# Sensors.net
KiCad netlist of a schematic drawn in Altium Designer
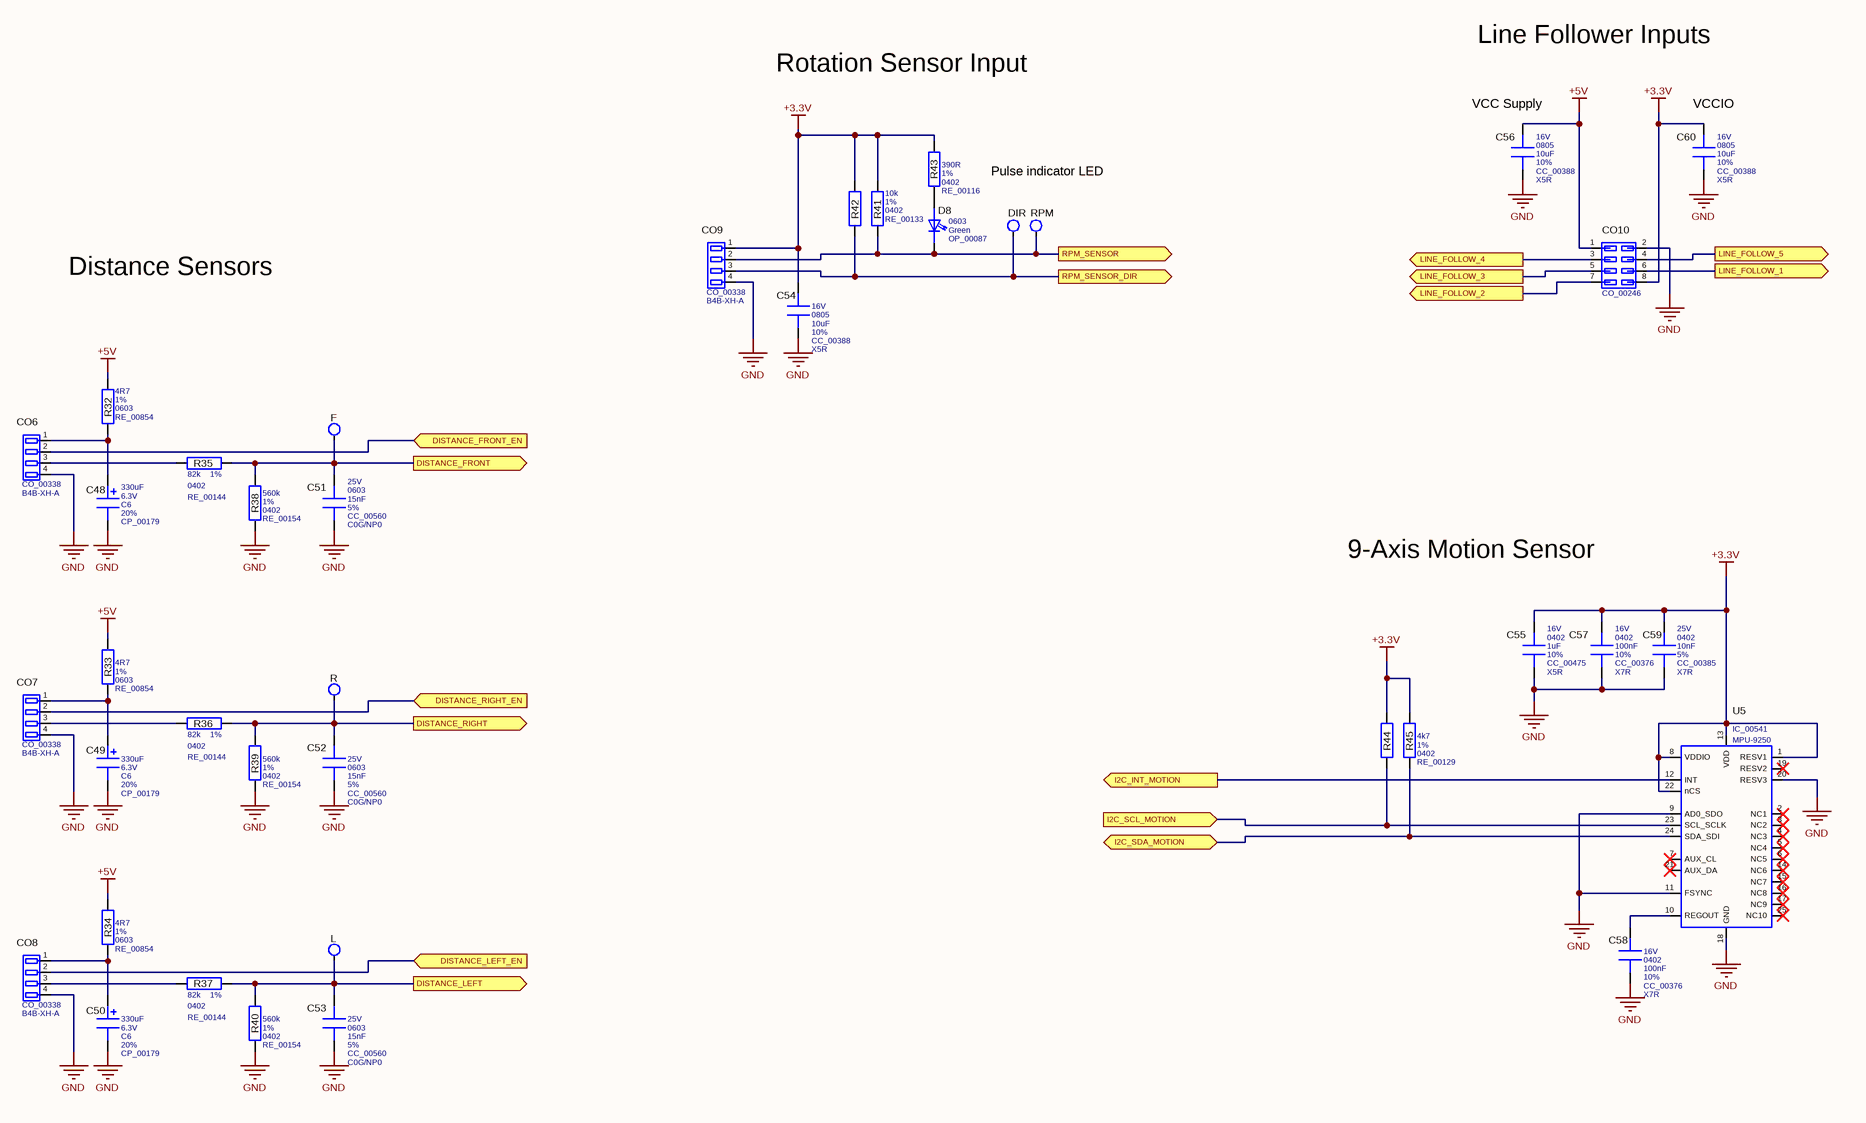
[diagram p0: Sensors.SchDoc]

(export (version "E")
  (design (tool "Eeschema 10.0.6"))
  (components
    (comp (ref "C48")
      (value "capacitor_polar")
      (footprint "CP_00179L")
      (fields
        (field (name "CAPACITANCE") "330uF")
        (field (name "VOLTAGE") "6.3V")
        (field (name "PACKAGE") "C6")
        (field (name "TOLERANCE") "20%")
        (field (name "PART_NUMBER") "CP_00179")
        (field (name "CREATOR") "Krenn Markus")
      )
      (libsource (lib "Central Library") (part "capacitor_polar"))
    )
    (comp (ref "C49")
      (value "capacitor_polar")
      (footprint "CP_00179L")
      (fields
        (field (name "CAPACITANCE") "330uF")
        (field (name "VOLTAGE") "6.3V")
        (field (name "PACKAGE") "C6")
        (field (name "TOLERANCE") "20%")
        (field (name "PART_NUMBER") "CP_00179")
        (field (name "CREATOR") "Krenn Markus")
      )
      (libsource (lib "Central Library") (part "capacitor_polar"))
    )
    (comp (ref "C50")
      (value "capacitor_polar")
      (footprint "CP_00179L")
      (fields
        (field (name "CAPACITANCE") "330uF")
        (field (name "VOLTAGE") "6.3V")
        (field (name "PACKAGE") "C6")
        (field (name "TOLERANCE") "20%")
        (field (name "PART_NUMBER") "CP_00179")
        (field (name "CREATOR") "Krenn Markus")
      )
      (libsource (lib "Central Library") (part "capacitor_polar"))
    )
    (comp (ref "C51")
      (value "capacitor")
      (footprint "CS1600X800X900X350X1250L")
      (fields
        (field (name "VOLTAGE") "25V")
        (field (name "PACKAGE") "0603")
        (field (name "CAPACITANCE") "15nF")
        (field (name "TOLERANCE") "5%")
        (field (name "PART_NUMBER") "CC_00560")
        (field (name "DIELECTRIC_MATERIAL") "C0G/NP0")
        (field (name "CREATOR") "Krenn Markus")
      )
      (libsource (lib "Central Library") (part "capacitor"))
    )
    (comp (ref "C52")
      (value "capacitor")
      (footprint "CS1600X800X900X350X1250L")
      (fields
        (field (name "VOLTAGE") "25V")
        (field (name "PACKAGE") "0603")
        (field (name "CAPACITANCE") "15nF")
        (field (name "TOLERANCE") "5%")
        (field (name "PART_NUMBER") "CC_00560")
        (field (name "DIELECTRIC_MATERIAL") "C0G/NP0")
        (field (name "CREATOR") "Krenn Markus")
      )
      (libsource (lib "Central Library") (part "capacitor"))
    )
    (comp (ref "C53")
      (value "capacitor")
      (footprint "CS1600X800X900X350X1250L")
      (fields
        (field (name "VOLTAGE") "25V")
        (field (name "PACKAGE") "0603")
        (field (name "CAPACITANCE") "15nF")
        (field (name "TOLERANCE") "5%")
        (field (name "PART_NUMBER") "CC_00560")
        (field (name "DIELECTRIC_MATERIAL") "C0G/NP0")
        (field (name "CREATOR") "Krenn Markus")
      )
      (libsource (lib "Central Library") (part "capacitor"))
    )
    (comp (ref "C54")
      (value "capacitor")
      (footprint "CS2000x1250x1250x350x1650L")
      (fields
        (field (name "VOLTAGE") "16V")
        (field (name "PACKAGE") "0805")
        (field (name "CAPACITANCE") "10uF")
        (field (name "TOLERANCE") "10%")
        (field (name "PART_NUMBER") "CC_00388")
        (field (name "DIELECTRIC_MATERIAL") "X5R")
        (field (name "CREATOR") "Krenn Markus")
      )
      (libsource (lib "Central Library") (part "capacitor"))
    )
    (comp (ref "C55")
      (value "capacitor")
      (footprint "CS1000X500X560X250X820L")
      (fields
        (field (name "VOLTAGE") "16V")
        (field (name "PACKAGE") "0402")
        (field (name "CAPACITANCE") "1uF")
        (field (name "TOLERANCE") "10%")
        (field (name "PART_NUMBER") "CC_00475")
        (field (name "DIELECTRIC_MATERIAL") "X5R")
        (field (name "CREATOR") "Krenn Markus")
      )
      (libsource (lib "Central Library") (part "capacitor"))
    )
    (comp (ref "C56")
      (value "capacitor")
      (footprint "CS2000x1250x1250x350x1650L")
      (fields
        (field (name "VOLTAGE") "16V")
        (field (name "PACKAGE") "0805")
        (field (name "CAPACITANCE") "10uF")
        (field (name "TOLERANCE") "10%")
        (field (name "PART_NUMBER") "CC_00388")
        (field (name "DIELECTRIC_MATERIAL") "X5R")
        (field (name "CREATOR") "Krenn Markus")
      )
      (libsource (lib "Central Library") (part "capacitor"))
    )
    (comp (ref "C57")
      (value "capacitor")
      (footprint "CS1000X500X560X250X820L")
      (fields
        (field (name "VOLTAGE") "16V")
        (field (name "PACKAGE") "0402")
        (field (name "CAPACITANCE") "100nF")
        (field (name "TOLERANCE") "10%")
        (field (name "PART_NUMBER") "CC_00376")
        (field (name "DIELECTRIC_MATERIAL") "X7R")
        (field (name "CREATOR") "Okorn Robert")
      )
      (libsource (lib "Central Library") (part "capacitor"))
    )
    (comp (ref "C58")
      (value "capacitor")
      (footprint "CS1000X500X560X250X820L")
      (fields
        (field (name "VOLTAGE") "16V")
        (field (name "PACKAGE") "0402")
        (field (name "CAPACITANCE") "100nF")
        (field (name "TOLERANCE") "10%")
        (field (name "PART_NUMBER") "CC_00376")
        (field (name "DIELECTRIC_MATERIAL") "X7R")
        (field (name "CREATOR") "Okorn Robert")
      )
      (libsource (lib "Central Library") (part "capacitor"))
    )
    (comp (ref "C59")
      (value "capacitor")
      (footprint "CS1000X500X560X250X820L")
      (fields
        (field (name "VOLTAGE") "25V")
        (field (name "PACKAGE") "0402")
        (field (name "CAPACITANCE") "10nF")
        (field (name "TOLERANCE") "5%")
        (field (name "PART_NUMBER") "CC_00385")
        (field (name "DIELECTRIC_MATERIAL") "X7R")
        (field (name "CREATOR") "Neissl Gernot")
      )
      (libsource (lib "Central Library") (part "capacitor"))
    )
    (comp (ref "C60")
      (value "capacitor")
      (footprint "CS2000x1250x1250x350x1650L")
      (fields
        (field (name "VOLTAGE") "16V")
        (field (name "PACKAGE") "0805")
        (field (name "CAPACITANCE") "10uF")
        (field (name "TOLERANCE") "10%")
        (field (name "PART_NUMBER") "CC_00388")
        (field (name "DIELECTRIC_MATERIAL") "X5R")
        (field (name "CREATOR") "Krenn Markus")
      )
      (libsource (lib "Central Library") (part "capacitor"))
    )
    (comp (ref "CO6")
      (value "header1x4")
      (footprint "CO_00338N")
      (description "XH connector - Disconnectable Crimp style connectors")
      (fields
        (field (name "POWER") "0W")
        (field (name "PART_NUMBER") "CO_00338")
        (field (name "MANUFACTURER_NUMBER") "B4B-XH-A")
        (field (name "CREATOR") "Krenn Markus")
      )
      (libsource (lib "Central Library") (part "header1x4"))
    )
    (comp (ref "CO7")
      (value "header1x4")
      (footprint "CO_00338N")
      (description "XH connector - Disconnectable Crimp style connectors")
      (fields
        (field (name "POWER") "0W")
        (field (name "PART_NUMBER") "CO_00338")
        (field (name "MANUFACTURER_NUMBER") "B4B-XH-A")
        (field (name "CREATOR") "Krenn Markus")
      )
      (libsource (lib "Central Library") (part "header1x4"))
    )
    (comp (ref "CO8")
      (value "header1x4")
      (footprint "CO_00338N")
      (description "XH connector - Disconnectable Crimp style connectors")
      (fields
        (field (name "POWER") "0W")
        (field (name "PART_NUMBER") "CO_00338")
        (field (name "MANUFACTURER_NUMBER") "B4B-XH-A")
        (field (name "CREATOR") "Krenn Markus")
      )
      (libsource (lib "Central Library") (part "header1x4"))
    )
    (comp (ref "CO9")
      (value "header1x4")
      (footprint "CO_00338N")
      (description "XH connector - Disconnectable Crimp style connectors")
      (fields
        (field (name "POWER") "0W")
        (field (name "PART_NUMBER") "CO_00338")
        (field (name "MANUFACTURER_NUMBER") "B4B-XH-A")
        (field (name "CREATOR") "Krenn Markus")
      )
      (libsource (lib "Central Library") (part "header1x4"))
    )
    (comp (ref "CO10")
      (value "header2x4")
      (footprint "CO_00246N")
      (description "SMT .025\" SQ POST HEADER")
      (fields
        (field (name "POWER") "0W")
        (field (name "PART_NUMBER") "CO_00246")
        (field (name "CREATOR") "Krenn Markus")
      )
      (libsource (lib "Central Library") (part "header2x4"))
    )
    (comp (ref "D8")
      (value "LED")
      (footprint "OP_00087L")
      (fields
        (field (name "PACKAGE") "0603")
        (field (name "COLOR") "Green")
        (field (name "PART_NUMBER") "OP_00087")
        (field (name "CREATOR") "Krenn Markus")
      )
      (libsource (lib "Central Library") (part "LED"))
    )
    (comp (ref "DIR")
      (value "testpoint")
      (footprint "CO_00057N")
      (description "Testpoint 1.6mm Bohrung 1mm")
      (fields
        (field (name "PART_NUMBER") "CO_00057")
        (field (name "POWER") "0W")
        (field (name "CREATOR") "Sirnik Heimo")
      )
      (libsource (lib "Central Library") (part "testpoint"))
    )
    (comp (ref "F")
      (value "testpoint")
      (footprint "CO_00057N")
      (description "Testpoint 1.6mm Bohrung 1mm")
      (fields
        (field (name "PART_NUMBER") "CO_00057")
        (field (name "POWER") "0W")
        (field (name "CREATOR") "Sirnik Heimo")
      )
      (libsource (lib "Central Library") (part "testpoint"))
    )
    (comp (ref "L")
      (value "testpoint")
      (footprint "CO_00057N")
      (description "Testpoint 1.6mm Bohrung 1mm")
      (fields
        (field (name "PART_NUMBER") "CO_00057")
        (field (name "POWER") "0W")
        (field (name "CREATOR") "Sirnik Heimo")
      )
      (libsource (lib "Central Library") (part "testpoint"))
    )
    (comp (ref "R")
      (value "testpoint")
      (footprint "CO_00057N")
      (description "Testpoint 1.6mm Bohrung 1mm")
      (fields
        (field (name "PART_NUMBER") "CO_00057")
        (field (name "POWER") "0W")
        (field (name "CREATOR") "Sirnik Heimo")
      )
      (libsource (lib "Central Library") (part "testpoint"))
    )
    (comp (ref "R32")
      (value "Resistor")
      (footprint "RS1600X850X450X300X1300L")
      (fields
        (field (name "RESISTANCE") "4R7")
        (field (name "TOLERANCE") "1%")
        (field (name "PACKAGE") "0603")
        (field (name "PART_NUMBER") "RE_00854")
        (field (name "CREATOR") "Krenn Markus")
      )
      (libsource (lib "Central Library") (part "Resistor"))
    )
    (comp (ref "R33")
      (value "Resistor")
      (footprint "RS1600X850X450X300X1300L")
      (fields
        (field (name "RESISTANCE") "4R7")
        (field (name "TOLERANCE") "1%")
        (field (name "PACKAGE") "0603")
        (field (name "PART_NUMBER") "RE_00854")
        (field (name "CREATOR") "Krenn Markus")
      )
      (libsource (lib "Central Library") (part "Resistor"))
    )
    (comp (ref "R34")
      (value "Resistor")
      (footprint "RS1600X850X450X300X1300L")
      (fields
        (field (name "RESISTANCE") "4R7")
        (field (name "TOLERANCE") "1%")
        (field (name "PACKAGE") "0603")
        (field (name "PART_NUMBER") "RE_00854")
        (field (name "CREATOR") "Krenn Markus")
      )
      (libsource (lib "Central Library") (part "Resistor"))
    )
    (comp (ref "R35")
      (value "Resistor")
      (footprint "RS1000X500X560X250X820L")
      (fields
        (field (name "RESISTANCE") "82k")
        (field (name "TOLERANCE") "1%")
        (field (name "PACKAGE") "0402")
        (field (name "PART_NUMBER") "RE_00144")
        (field (name "CREATOR") "Krenn Markus")
      )
      (libsource (lib "Central Library") (part "Resistor"))
    )
    (comp (ref "R36")
      (value "Resistor")
      (footprint "RS1000X500X560X250X820L")
      (fields
        (field (name "RESISTANCE") "82k")
        (field (name "TOLERANCE") "1%")
        (field (name "PACKAGE") "0402")
        (field (name "PART_NUMBER") "RE_00144")
        (field (name "CREATOR") "Krenn Markus")
      )
      (libsource (lib "Central Library") (part "Resistor"))
    )
    (comp (ref "R37")
      (value "Resistor")
      (footprint "RS1000X500X560X250X820L")
      (fields
        (field (name "RESISTANCE") "82k")
        (field (name "TOLERANCE") "1%")
        (field (name "PACKAGE") "0402")
        (field (name "PART_NUMBER") "RE_00144")
        (field (name "CREATOR") "Krenn Markus")
      )
      (libsource (lib "Central Library") (part "Resistor"))
    )
    (comp (ref "R38")
      (value "Resistor")
      (footprint "RS1000X500X560X250X820L")
      (fields
        (field (name "RESISTANCE") "560k")
        (field (name "TOLERANCE") "1%")
        (field (name "PACKAGE") "0402")
        (field (name "PART_NUMBER") "RE_00154")
        (field (name "CREATOR") "Krenn Markus")
      )
      (libsource (lib "Central Library") (part "Resistor"))
    )
    (comp (ref "R39")
      (value "Resistor")
      (footprint "RS1000X500X560X250X820L")
      (fields
        (field (name "RESISTANCE") "560k")
        (field (name "TOLERANCE") "1%")
        (field (name "PACKAGE") "0402")
        (field (name "PART_NUMBER") "RE_00154")
        (field (name "CREATOR") "Krenn Markus")
      )
      (libsource (lib "Central Library") (part "Resistor"))
    )
    (comp (ref "R40")
      (value "Resistor")
      (footprint "RS1000X500X560X250X820L")
      (fields
        (field (name "RESISTANCE") "560k")
        (field (name "TOLERANCE") "1%")
        (field (name "PACKAGE") "0402")
        (field (name "PART_NUMBER") "RE_00154")
        (field (name "CREATOR") "Krenn Markus")
      )
      (libsource (lib "Central Library") (part "Resistor"))
    )
    (comp (ref "R41")
      (value "Resistor")
      (footprint "RS1000X500X560X250X820L")
      (fields
        (field (name "RESISTANCE") "10k")
        (field (name "TOLERANCE") "1%")
        (field (name "PACKAGE") "0402")
        (field (name "PART_NUMBER") "RE_00133")
        (field (name "CREATOR") "Krenn Markus")
      )
      (libsource (lib "Central Library") (part "Resistor"))
    )
    (comp (ref "R42")
      (value "Resistor")
      (footprint "RS1000X500X560X250X820L")
      (fields
        (field (name "TOLERANCE") "1%")
        (field (name "PART_NUMBER") "RE_00133")
        (field (name "CREATOR") "Krenn Markus")
      )
      (libsource (lib "Central Library") (part "Resistor"))
    )
    (comp (ref "R43")
      (value "Resistor")
      (footprint "RS1000X500X560X250X820L")
      (fields
        (field (name "RESISTANCE") "390R")
        (field (name "TOLERANCE") "1%")
        (field (name "PACKAGE") "0402")
        (field (name "PART_NUMBER") "RE_00116")
        (field (name "CREATOR") "Krenn Markus")
      )
      (libsource (lib "Central Library") (part "Resistor"))
    )
    (comp (ref "R44")
      (value "Resistor")
      (footprint "RS1000X500X560X250X820L")
      (fields
        (field (name "TOLERANCE") "1%")
        (field (name "PART_NUMBER") "RE_00129")
        (field (name "CREATOR") "Krenn Markus")
      )
      (libsource (lib "Central Library") (part "Resistor"))
    )
    (comp (ref "R45")
      (value "Resistor")
      (footprint "RS1000X500X560X250X820L")
      (fields
        (field (name "RESISTANCE") "4k7")
        (field (name "TOLERANCE") "1%")
        (field (name "PACKAGE") "0402")
        (field (name "PART_NUMBER") "RE_00129")
        (field (name "CREATOR") "Krenn Markus")
      )
      (libsource (lib "Central Library") (part "Resistor"))
    )
    (comp (ref "RPM")
      (value "testpoint")
      (footprint "CO_00057N")
      (description "Testpoint 1.6mm Bohrung 1mm")
      (fields
        (field (name "PART_NUMBER") "CO_00057")
        (field (name "POWER") "0W")
        (field (name "CREATOR") "Sirnik Heimo")
      )
      (libsource (lib "Central Library") (part "testpoint"))
    )
    (comp (ref "U5")
      (value "IC_00541")
      (footprint "IC_00541N")
      (description "MPU-9250 - GYRO/ACCEL/COMPASS, 9ACHSEN, I2C, QFN-24")
      (fields
        (field (name "PART_NUMBER") "IC_00541")
        (field (name "MANUFACTURER_NUMBER") "MPU-9250")
        (field (name "CREATOR") "Sirnik Heimo")
      )
      (libsource (lib "Central Library") (part "IC_00541"))
    )
  )
  (nets
    (net (code "1") (name "+3.3V") (class "Default")
      (node (ref "C54") (pin "2") (pinfunction "PIN2_2") (pintype "passive"))
      (node (ref "C55") (pin "2") (pinfunction "PIN2_2") (pintype "passive"))
      (node (ref "C57") (pin "2") (pinfunction "PIN2_2") (pintype "passive"))
      (node (ref "C59") (pin "2") (pinfunction "PIN2_2") (pintype "passive"))
      (node (ref "C60") (pin "2") (pinfunction "PIN2_2") (pintype "passive"))
      (node (ref "CO10") (pin "8") (pinfunction "PIN8_8") (pintype "passive"))
      (node (ref "CO9") (pin "1") (pinfunction "PIN1_1") (pintype "passive"))
      (node (ref "R41") (pin "2") (pinfunction "PIN2_2") (pintype "passive"))
      (node (ref "R42") (pin "2") (pinfunction "PIN2_2") (pintype "passive"))
      (node (ref "R43") (pin "2") (pinfunction "PIN2_2") (pintype "passive"))
      (node (ref "R44") (pin "2") (pinfunction "PIN2_2") (pintype "passive"))
      (node (ref "R45") (pin "2") (pinfunction "PIN2_2") (pintype "passive"))
      (node (ref "U5") (pin "1") (pinfunction "RESV1_1") (pintype "passive"))
      (node (ref "U5") (pin "13") (pinfunction "VDD_13") (pintype "passive"))
      (node (ref "U5") (pin "22") (pinfunction "nCS_22") (pintype "passive"))
      (node (ref "U5") (pin "8") (pinfunction "VDDIO_8") (pintype "passive"))
    )
    (net (code "2") (name "+5V") (class "Default")
      (node (ref "C56") (pin "2") (pinfunction "PIN2_2") (pintype "passive"))
      (node (ref "CO10") (pin "1") (pinfunction "PIN1_1") (pintype "passive"))
      (node (ref "R32") (pin "2") (pinfunction "PIN2_2") (pintype "passive"))
      (node (ref "R33") (pin "2") (pinfunction "PIN2_2") (pintype "passive"))
      (node (ref "R34") (pin "2") (pinfunction "PIN2_2") (pintype "passive"))
    )
    (net (code "3") (name "/DISTANCE_FRONT") (class "Default")
      (node (ref "C51") (pin "2") (pinfunction "PIN2_2") (pintype "passive"))
      (node (ref "F") (pin "1") (pinfunction "PIN1_1") (pintype "passive"))
      (node (ref "R35") (pin "2") (pinfunction "PIN2_2") (pintype "passive"))
      (node (ref "R38") (pin "2") (pinfunction "PIN2_2") (pintype "passive"))
    )
    (net (code "4") (name "/DISTANCE_FRONT_EN") (class "Default")
      (node (ref "CO6") (pin "2") (pinfunction "PIN2_2") (pintype "passive"))
    )
    (net (code "5") (name "/DISTANCE_LEFT") (class "Default")
      (node (ref "C53") (pin "2") (pinfunction "PIN2_2") (pintype "passive"))
      (node (ref "L") (pin "1") (pinfunction "PIN1_1") (pintype "passive"))
      (node (ref "R37") (pin "2") (pinfunction "PIN2_2") (pintype "passive"))
      (node (ref "R40") (pin "2") (pinfunction "PIN2_2") (pintype "passive"))
    )
    (net (code "6") (name "/DISTANCE_LEFT_EN") (class "Default")
      (node (ref "CO8") (pin "2") (pinfunction "PIN2_2") (pintype "passive"))
    )
    (net (code "7") (name "/DISTANCE_RIGHT") (class "Default")
      (node (ref "C52") (pin "2") (pinfunction "PIN2_2") (pintype "passive"))
      (node (ref "R") (pin "1") (pinfunction "PIN1_1") (pintype "passive"))
      (node (ref "R36") (pin "2") (pinfunction "PIN2_2") (pintype "passive"))
      (node (ref "R39") (pin "2") (pinfunction "PIN2_2") (pintype "passive"))
    )
    (net (code "8") (name "/DISTANCE_RIGHT_EN") (class "Default")
      (node (ref "CO7") (pin "2") (pinfunction "PIN2_2") (pintype "passive"))
    )
    (net (code "9") (name "/I2C_INT_MOTION") (class "Default")
      (node (ref "U5") (pin "12") (pinfunction "INT_12") (pintype "passive"))
    )
    (net (code "10") (name "/I2C_SCL_MOTION") (class "Default")
      (node (ref "R44") (pin "1") (pinfunction "PIN1_1") (pintype "passive"))
      (node (ref "U5") (pin "23") (pinfunction "SCL_SCLK_23") (pintype "passive"))
    )
    (net (code "11") (name "/I2C_SDA_MOTION") (class "Default")
      (node (ref "R45") (pin "1") (pinfunction "PIN1_1") (pintype "passive"))
      (node (ref "U5") (pin "24") (pinfunction "SDA_SDI_24") (pintype "passive"))
    )
    (net (code "12") (name "/LINE_FOLLOW_1") (class "Default")
      (node (ref "CO10") (pin "6") (pinfunction "PIN6_6") (pintype "passive"))
    )
    (net (code "13") (name "/LINE_FOLLOW_2") (class "Default")
      (node (ref "CO10") (pin "7") (pinfunction "PIN7_7") (pintype "passive"))
    )
    (net (code "14") (name "/LINE_FOLLOW_3") (class "Default")
      (node (ref "CO10") (pin "5") (pinfunction "PIN5_5") (pintype "passive"))
    )
    (net (code "15") (name "/LINE_FOLLOW_4") (class "Default")
      (node (ref "CO10") (pin "3") (pinfunction "PIN3_3") (pintype "passive"))
    )
    (net (code "16") (name "/LINE_FOLLOW_5") (class "Default")
      (node (ref "CO10") (pin "4") (pinfunction "PIN4_4") (pintype "passive"))
    )
    (net (code "17") (name "/RPM_SENSOR") (class "Default")
      (node (ref "CO9") (pin "2") (pinfunction "PIN2_2") (pintype "passive"))
      (node (ref "D8") (pin "1") (pinfunction "CATHODE_1") (pintype "passive"))
      (node (ref "R41") (pin "1") (pinfunction "PIN1_1") (pintype "passive"))
      (node (ref "RPM") (pin "1") (pinfunction "PIN1_1") (pintype "passive"))
    )
    (net (code "18") (name "/RPM_SENSOR_DIR") (class "Default")
      (node (ref "CO9") (pin "3") (pinfunction "PIN3_3") (pintype "passive"))
      (node (ref "DIR") (pin "1") (pinfunction "PIN1_1") (pintype "passive"))
      (node (ref "R42") (pin "1") (pinfunction "PIN1_1") (pintype "passive"))
    )
    (net (code "19") (name "GND") (class "Default")
      (node (ref "C48") (pin "2") (pinfunction "PIN2_2") (pintype "passive"))
      (node (ref "C49") (pin "2") (pinfunction "PIN2_2") (pintype "passive"))
      (node (ref "C50") (pin "2") (pinfunction "PIN2_2") (pintype "passive"))
      (node (ref "C51") (pin "1") (pinfunction "PIN1_1") (pintype "passive"))
      (node (ref "C52") (pin "1") (pinfunction "PIN1_1") (pintype "passive"))
      (node (ref "C53") (pin "1") (pinfunction "PIN1_1") (pintype "passive"))
      (node (ref "C54") (pin "1") (pinfunction "PIN1_1") (pintype "passive"))
      (node (ref "C55") (pin "1") (pinfunction "PIN1_1") (pintype "passive"))
      (node (ref "C56") (pin "1") (pinfunction "PIN1_1") (pintype "passive"))
      (node (ref "C57") (pin "1") (pinfunction "PIN1_1") (pintype "passive"))
      (node (ref "C58") (pin "1") (pinfunction "PIN1_1") (pintype "passive"))
      (node (ref "C59") (pin "1") (pinfunction "PIN1_1") (pintype "passive"))
      (node (ref "C60") (pin "1") (pinfunction "PIN1_1") (pintype "passive"))
      (node (ref "CO10") (pin "2") (pinfunction "PIN2_2") (pintype "passive"))
      (node (ref "CO6") (pin "4") (pinfunction "PIN4_4") (pintype "passive"))
      (node (ref "CO7") (pin "4") (pinfunction "PIN4_4") (pintype "passive"))
      (node (ref "CO8") (pin "4") (pinfunction "PIN4_4") (pintype "passive"))
      (node (ref "CO9") (pin "4") (pinfunction "PIN4_4") (pintype "passive"))
      (node (ref "R38") (pin "1") (pinfunction "PIN1_1") (pintype "passive"))
      (node (ref "R39") (pin "1") (pinfunction "PIN1_1") (pintype "passive"))
      (node (ref "R40") (pin "1") (pinfunction "PIN1_1") (pintype "passive"))
      (node (ref "U5") (pin "11") (pinfunction "FSYNC_11") (pintype "passive"))
      (node (ref "U5") (pin "18") (pinfunction "GND_18") (pintype "passive"))
      (node (ref "U5") (pin "20") (pinfunction "RESV3_20") (pintype "passive"))
      (node (ref "U5") (pin "9") (pinfunction "AD0_SDO_9") (pintype "passive"))
    )
    (net (code "20") (name "Net-(C48-PIN1)") (class "Default")
      (node (ref "C48") (pin "1") (pinfunction "PIN1_1") (pintype "passive"))
      (node (ref "CO6") (pin "1") (pinfunction "PIN1_1") (pintype "passive"))
      (node (ref "R32") (pin "1") (pinfunction "PIN1_1") (pintype "passive"))
    )
    (net (code "21") (name "Net-(C49-PIN1)") (class "Default")
      (node (ref "C49") (pin "1") (pinfunction "PIN1_1") (pintype "passive"))
      (node (ref "CO7") (pin "1") (pinfunction "PIN1_1") (pintype "passive"))
      (node (ref "R33") (pin "1") (pinfunction "PIN1_1") (pintype "passive"))
    )
    (net (code "22") (name "Net-(C50-PIN1)") (class "Default")
      (node (ref "C50") (pin "1") (pinfunction "PIN1_1") (pintype "passive"))
      (node (ref "CO8") (pin "1") (pinfunction "PIN1_1") (pintype "passive"))
      (node (ref "R34") (pin "1") (pinfunction "PIN1_1") (pintype "passive"))
    )
    (net (code "23") (name "Net-(C58-PIN2)") (class "Default")
      (node (ref "C58") (pin "2") (pinfunction "PIN2_2") (pintype "passive"))
      (node (ref "U5") (pin "10") (pinfunction "REGOUT_10") (pintype "passive"))
    )
    (net (code "24") (name "Net-(CO6-PIN3)") (class "Default")
      (node (ref "CO6") (pin "3") (pinfunction "PIN3_3") (pintype "passive"))
      (node (ref "R35") (pin "1") (pinfunction "PIN1_1") (pintype "passive"))
    )
    (net (code "25") (name "Net-(CO7-PIN3)") (class "Default")
      (node (ref "CO7") (pin "3") (pinfunction "PIN3_3") (pintype "passive"))
      (node (ref "R36") (pin "1") (pinfunction "PIN1_1") (pintype "passive"))
    )
    (net (code "26") (name "Net-(CO8-PIN3)") (class "Default")
      (node (ref "CO8") (pin "3") (pinfunction "PIN3_3") (pintype "passive"))
      (node (ref "R37") (pin "1") (pinfunction "PIN1_1") (pintype "passive"))
    )
    (net (code "27") (name "Net-(D8-ANODE)") (class "Default")
      (node (ref "D8") (pin "2") (pinfunction "ANODE_2") (pintype "passive"))
      (node (ref "R43") (pin "1") (pinfunction "PIN1_1") (pintype "passive"))
    )
    (net (code "28") (name "unconnected-(U5-AUX_CL-Pad7)") (class "Default")
      (node (ref "U5") (pin "7") (pinfunction "AUX_CL_7") (pintype "passive+no_connect"))
    )
    (net (code "29") (name "unconnected-(U5-AUX_DA-Pad21)") (class "Default")
      (node (ref "U5") (pin "21") (pinfunction "AUX_DA_21") (pintype "passive+no_connect"))
    )
    (net (code "30") (name "unconnected-(U5-NC1-Pad2)") (class "Default")
      (node (ref "U5") (pin "2") (pinfunction "NC1_2") (pintype "passive+no_connect"))
    )
    (net (code "31") (name "unconnected-(U5-NC2-Pad3)") (class "Default")
      (node (ref "U5") (pin "3") (pinfunction "NC2_3") (pintype "passive+no_connect"))
    )
    (net (code "32") (name "unconnected-(U5-NC3-Pad4)") (class "Default")
      (node (ref "U5") (pin "4") (pinfunction "NC3_4") (pintype "passive+no_connect"))
    )
    (net (code "33") (name "unconnected-(U5-NC4-Pad5)") (class "Default")
      (node (ref "U5") (pin "5") (pinfunction "NC4_5") (pintype "passive+no_connect"))
    )
    (net (code "34") (name "unconnected-(U5-NC5-Pad6)") (class "Default")
      (node (ref "U5") (pin "6") (pinfunction "NC5_6") (pintype "passive+no_connect"))
    )
    (net (code "35") (name "unconnected-(U5-NC6-Pad14)") (class "Default")
      (node (ref "U5") (pin "14") (pinfunction "NC6_14") (pintype "passive+no_connect"))
    )
    (net (code "36") (name "unconnected-(U5-NC7-Pad15)") (class "Default")
      (node (ref "U5") (pin "15") (pinfunction "NC7_15") (pintype "passive+no_connect"))
    )
    (net (code "37") (name "unconnected-(U5-NC8-Pad16)") (class "Default")
      (node (ref "U5") (pin "16") (pinfunction "NC8_16") (pintype "passive+no_connect"))
    )
    (net (code "38") (name "unconnected-(U5-NC9-Pad17)") (class "Default")
      (node (ref "U5") (pin "17") (pinfunction "NC9_17") (pintype "passive+no_connect"))
    )
    (net (code "39") (name "unconnected-(U5-NC10-Pad25)") (class "Default")
      (node (ref "U5") (pin "25") (pinfunction "NC10_25") (pintype "passive+no_connect"))
    )
    (net (code "40") (name "unconnected-(U5-RESV2-Pad19)") (class "Default")
      (node (ref "U5") (pin "19") (pinfunction "RESV2_19") (pintype "passive+no_connect"))
    )
  )
)
